# Robot_Psoc.net
KiCad netlist of a schematic drawn in EAGLE
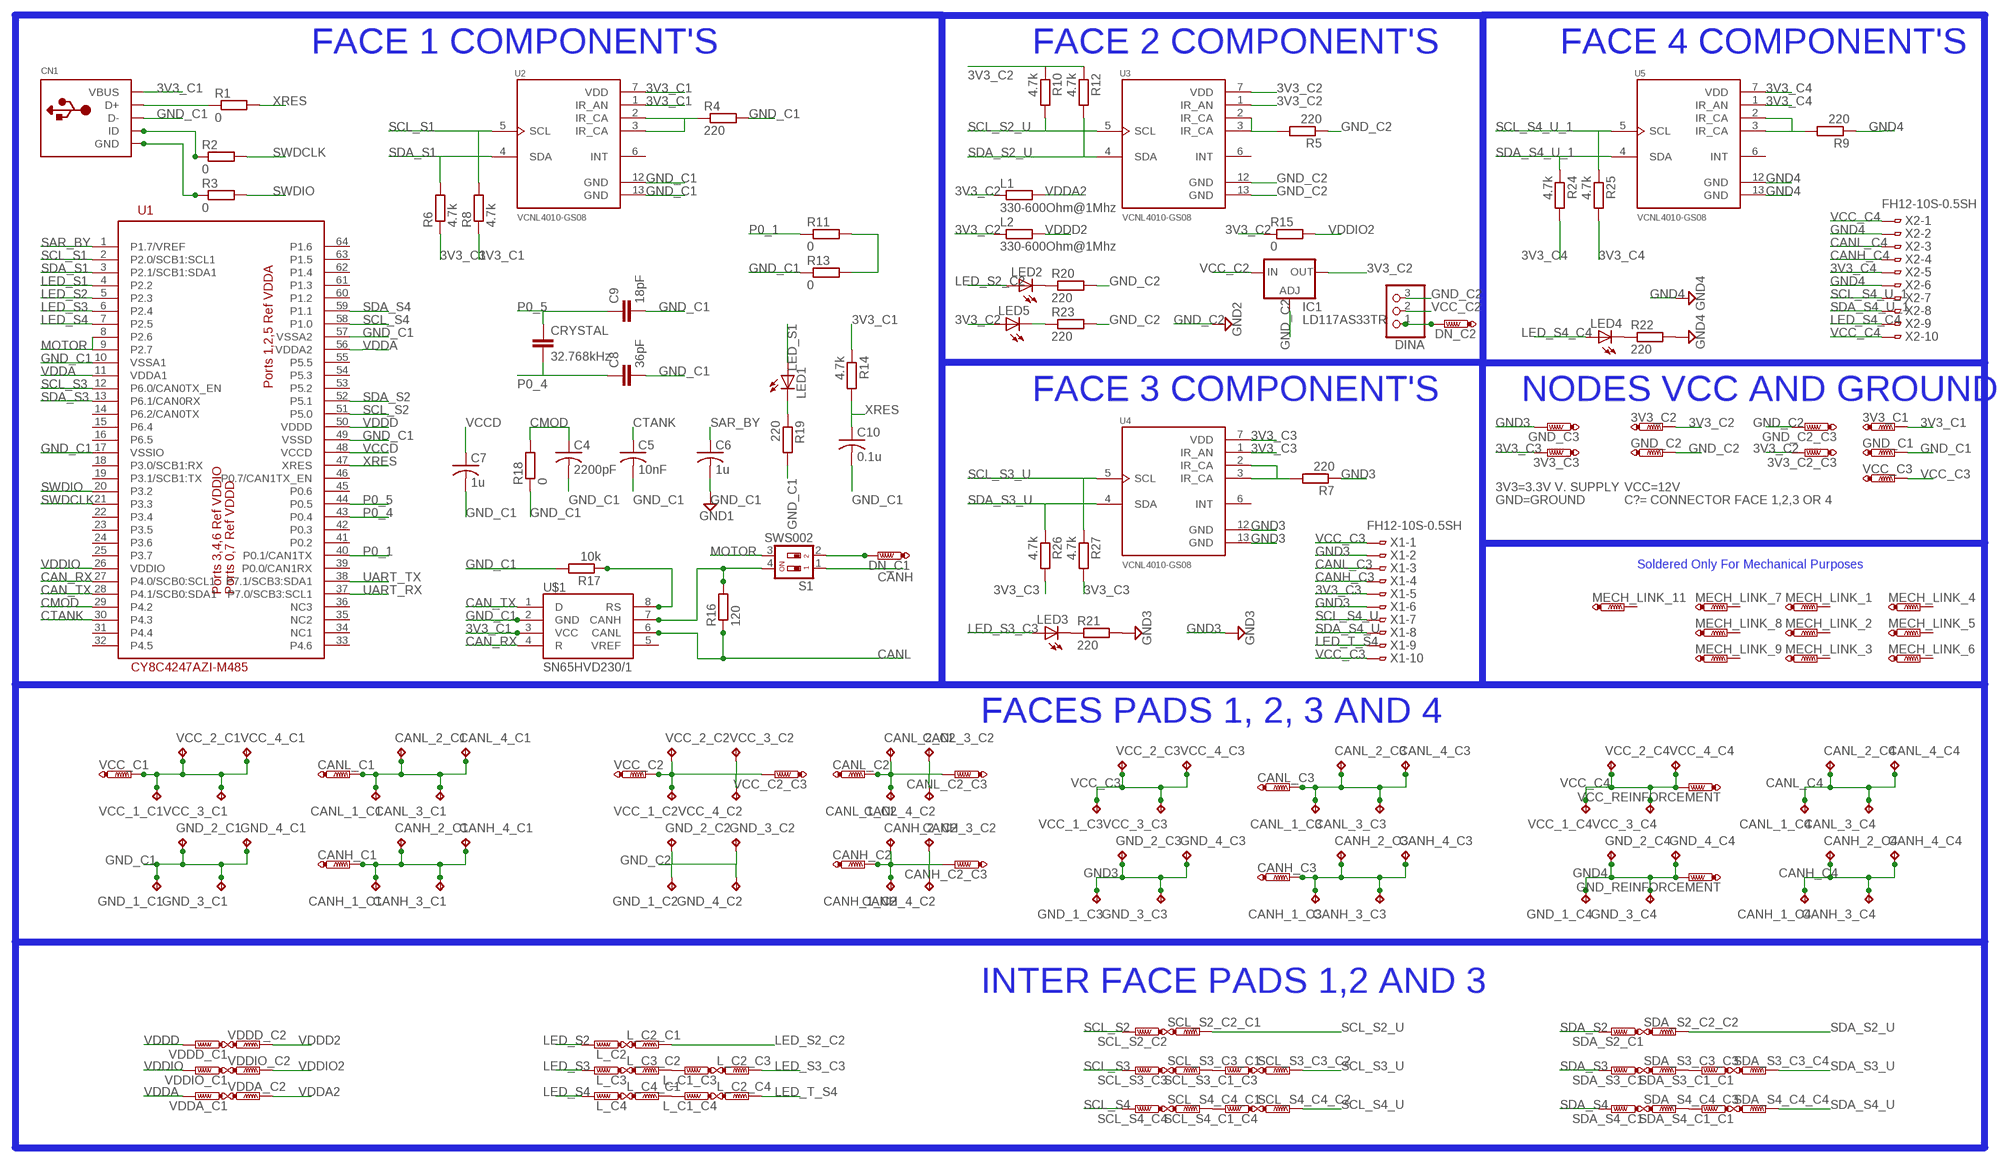
[diagram p0: schematic, sheet 1]

(export (version "E")
  (design (tool "Eeschema 10.0.6"))
  (components
    (comp (ref "3V3_C1")
      (value "PTR1TP11R")
      (footprint "eagle-import:TP11R")
      (libsource (lib "eagle-import") (part "PTR1TP11R"))
    )
    (comp (ref "3V3_C2")
      (value "PTR1TP11R")
      (footprint "eagle-import:TP11R")
      (libsource (lib "eagle-import") (part "PTR1TP11R"))
    )
    (comp (ref "3V3_C2_C3")
      (value "PTR1TP11R")
      (footprint "eagle-import:TP11R")
      (libsource (lib "eagle-import") (part "PTR1TP11R"))
    )
    (comp (ref "3V3_C3")
      (value "PTR1TP11R")
      (footprint "eagle-import:TP11R")
      (libsource (lib "eagle-import") (part "PTR1TP11R"))
    )
    (comp (ref "C4")
      (value "2200pF")
      (footprint "eagle-import:C0805")
      (libsource (lib "eagle-import") (part "C-USC0805"))
    )
    (comp (ref "C5")
      (value "10nF")
      (footprint "eagle-import:C0805")
      (libsource (lib "eagle-import") (part "C-USC0805"))
    )
    (comp (ref "C6")
      (value "1u")
      (footprint "eagle-import:C0805")
      (libsource (lib "eagle-import") (part "C-USC0805"))
    )
    (comp (ref "C7")
      (value "1u")
      (footprint "eagle-import:C0805")
      (libsource (lib "eagle-import") (part "C-USC0805"))
    )
    (comp (ref "C8")
      (value "36pF")
      (footprint "eagle-import:C0805")
      (libsource (lib "eagle-import") (part "C-EUC0805"))
    )
    (comp (ref "C9")
      (value "18pF")
      (footprint "eagle-import:C0805")
      (libsource (lib "eagle-import") (part "C-EUC0805"))
    )
    (comp (ref "C10")
      (value "0.1u")
      (footprint "eagle-import:C0805")
      (libsource (lib "eagle-import") (part "C-USC0805"))
    )
    (comp (ref "CANH_1_C1")
      (value "TPB2,54")
      (footprint "eagle-import:B2,54")
      (libsource (lib "eagle-import") (part "TPB2,54"))
    )
    (comp (ref "CANH_1_C2")
      (value "TPB2,54")
      (footprint "eagle-import:B2,54")
      (libsource (lib "eagle-import") (part "TPB2,54"))
    )
    (comp (ref "CANH_1_C3")
      (value "TPB2,54")
      (footprint "eagle-import:B2,54")
      (libsource (lib "eagle-import") (part "TPB2,54"))
    )
    (comp (ref "CANH_1_C4")
      (value "TPB2,54")
      (footprint "eagle-import:B2,54")
      (libsource (lib "eagle-import") (part "TPB2,54"))
    )
    (comp (ref "CANH_2_C1")
      (value "TPB2,54")
      (footprint "eagle-import:B2,54")
      (libsource (lib "eagle-import") (part "TPB2,54"))
    )
    (comp (ref "CANH_2_C2")
      (value "TPB2,54")
      (footprint "eagle-import:B2,54")
      (libsource (lib "eagle-import") (part "TPB2,54"))
    )
    (comp (ref "CANH_2_C3")
      (value "TPB2,54")
      (footprint "eagle-import:B2,54")
      (libsource (lib "eagle-import") (part "TPB2,54"))
    )
    (comp (ref "CANH_2_C4")
      (value "TPB2,54")
      (footprint "eagle-import:B2,54")
      (libsource (lib "eagle-import") (part "TPB2,54"))
    )
    (comp (ref "CANH_3_C1")
      (value "TPB2,54")
      (footprint "eagle-import:B2,54")
      (libsource (lib "eagle-import") (part "TPB2,54"))
    )
    (comp (ref "CANH_3_C2")
      (value "TPB2,54")
      (footprint "eagle-import:B2,54")
      (libsource (lib "eagle-import") (part "TPB2,54"))
    )
    (comp (ref "CANH_3_C3")
      (value "TPB2,54")
      (footprint "eagle-import:B2,54")
      (libsource (lib "eagle-import") (part "TPB2,54"))
    )
    (comp (ref "CANH_3_C4")
      (value "TPB2,54")
      (footprint "eagle-import:B2,54")
      (libsource (lib "eagle-import") (part "TPB2,54"))
    )
    (comp (ref "CANH_4_C1")
      (value "TPB2,54")
      (footprint "eagle-import:B2,54")
      (libsource (lib "eagle-import") (part "TPB2,54"))
    )
    (comp (ref "CANH_4_C2")
      (value "TPB2,54")
      (footprint "eagle-import:B2,54")
      (libsource (lib "eagle-import") (part "TPB2,54"))
    )
    (comp (ref "CANH_4_C3")
      (value "TPB2,54")
      (footprint "eagle-import:B2,54")
      (libsource (lib "eagle-import") (part "TPB2,54"))
    )
    (comp (ref "CANH_4_C4")
      (value "TPB2,54")
      (footprint "eagle-import:B2,54")
      (libsource (lib "eagle-import") (part "TPB2,54"))
    )
    (comp (ref "CANH_C1")
      (value "PTR1TP11R")
      (footprint "eagle-import:TP11R")
      (libsource (lib "eagle-import") (part "PTR1TP11R"))
    )
    (comp (ref "CANH_C2")
      (value "PTR1TP11R")
      (footprint "eagle-import:TP11R")
      (libsource (lib "eagle-import") (part "PTR1TP11R"))
    )
    (comp (ref "CANH_C2_C3")
      (value "PTR1TP11R")
      (footprint "eagle-import:TP11R")
      (libsource (lib "eagle-import") (part "PTR1TP11R"))
    )
    (comp (ref "CANH_C3")
      (value "PTR1TP11R")
      (footprint "eagle-import:TP11R")
      (libsource (lib "eagle-import") (part "PTR1TP11R"))
    )
    (comp (ref "CANL_1_C1")
      (value "TPB2,54")
      (footprint "eagle-import:B2,54")
      (libsource (lib "eagle-import") (part "TPB2,54"))
    )
    (comp (ref "CANL_1_C2")
      (value "TPB2,54")
      (footprint "eagle-import:B2,54")
      (libsource (lib "eagle-import") (part "TPB2,54"))
    )
    (comp (ref "CANL_1_C3")
      (value "TPB2,54")
      (footprint "eagle-import:B2,54")
      (libsource (lib "eagle-import") (part "TPB2,54"))
    )
    (comp (ref "CANL_1_C4")
      (value "TPB2,54")
      (footprint "eagle-import:B2,54")
      (libsource (lib "eagle-import") (part "TPB2,54"))
    )
    (comp (ref "CANL_2_C1")
      (value "TPB2,54")
      (footprint "eagle-import:B2,54")
      (libsource (lib "eagle-import") (part "TPB2,54"))
    )
    (comp (ref "CANL_2_C2")
      (value "TPB2,54")
      (footprint "eagle-import:B2,54")
      (libsource (lib "eagle-import") (part "TPB2,54"))
    )
    (comp (ref "CANL_2_C3")
      (value "TPB2,54")
      (footprint "eagle-import:B2,54")
      (libsource (lib "eagle-import") (part "TPB2,54"))
    )
    (comp (ref "CANL_2_C4")
      (value "TPB2,54")
      (footprint "eagle-import:B2,54")
      (libsource (lib "eagle-import") (part "TPB2,54"))
    )
    (comp (ref "CANL_3_C1")
      (value "TPB2,54")
      (footprint "eagle-import:B2,54")
      (libsource (lib "eagle-import") (part "TPB2,54"))
    )
    (comp (ref "CANL_3_C2")
      (value "TPB2,54")
      (footprint "eagle-import:B2,54")
      (libsource (lib "eagle-import") (part "TPB2,54"))
    )
    (comp (ref "CANL_3_C3")
      (value "TPB2,54")
      (footprint "eagle-import:B2,54")
      (libsource (lib "eagle-import") (part "TPB2,54"))
    )
    (comp (ref "CANL_3_C4")
      (value "TPB2,54")
      (footprint "eagle-import:B2,54")
      (libsource (lib "eagle-import") (part "TPB2,54"))
    )
    (comp (ref "CANL_4_C1")
      (value "TPB2,54")
      (footprint "eagle-import:B2,54")
      (libsource (lib "eagle-import") (part "TPB2,54"))
    )
    (comp (ref "CANL_4_C2")
      (value "TPB2,54")
      (footprint "eagle-import:B2,54")
      (libsource (lib "eagle-import") (part "TPB2,54"))
    )
    (comp (ref "CANL_4_C3")
      (value "TPB2,54")
      (footprint "eagle-import:B2,54")
      (libsource (lib "eagle-import") (part "TPB2,54"))
    )
    (comp (ref "CANL_4_C4")
      (value "TPB2,54")
      (footprint "eagle-import:B2,54")
      (libsource (lib "eagle-import") (part "TPB2,54"))
    )
    (comp (ref "CANL_C1")
      (value "PTR1TP11R")
      (footprint "eagle-import:TP11R")
      (libsource (lib "eagle-import") (part "PTR1TP11R"))
    )
    (comp (ref "CANL_C2")
      (value "PTR1TP11R")
      (footprint "eagle-import:TP11R")
      (libsource (lib "eagle-import") (part "PTR1TP11R"))
    )
    (comp (ref "CANL_C2_C3")
      (value "PTR1TP11R")
      (footprint "eagle-import:TP11R")
      (libsource (lib "eagle-import") (part "PTR1TP11R"))
    )
    (comp (ref "CANL_C3")
      (value "PTR1TP11R")
      (footprint "eagle-import:TP11R")
      (libsource (lib "eagle-import") (part "PTR1TP11R"))
    )
    (comp (ref "CN1")
      (value "USBMINIB")
      (footprint "eagle-import:USB-MINIB")
      (libsource (lib "eagle-import") (part "USBMINIB"))
    )
    (comp (ref "CRYSTAL")
      (value "32.768kHz")
      (footprint "eagle-import:C0603")
      (libsource (lib "eagle-import") (part "C-EUC0603"))
    )
    (comp (ref "DINA")
      (value "PINHD-1X3")
      (footprint "eagle-import:1X03")
      (libsource (lib "eagle-import") (part "PINHD-1X3"))
    )
    (comp (ref "DN_C1")
      (value "PTR1TP11R")
      (footprint "eagle-import:TP11R")
      (libsource (lib "eagle-import") (part "PTR1TP11R"))
    )
    (comp (ref "DN_C2")
      (value "PTR1TP11R")
      (footprint "eagle-import:TP11R")
      (libsource (lib "eagle-import") (part "PTR1TP11R"))
    )
    (comp (ref "GND_1_C1")
      (value "TPB2,54")
      (footprint "eagle-import:B2,54")
      (libsource (lib "eagle-import") (part "TPB2,54"))
    )
    (comp (ref "GND_1_C2")
      (value "TPB2,54")
      (footprint "eagle-import:B2,54")
      (libsource (lib "eagle-import") (part "TPB2,54"))
    )
    (comp (ref "GND_1_C3")
      (value "TPB2,54")
      (footprint "eagle-import:B2,54")
      (libsource (lib "eagle-import") (part "TPB2,54"))
    )
    (comp (ref "GND_1_C4")
      (value "TPB2,54")
      (footprint "eagle-import:B2,54")
      (libsource (lib "eagle-import") (part "TPB2,54"))
    )
    (comp (ref "GND_2_C1")
      (value "TPB2,54")
      (footprint "eagle-import:B2,54")
      (libsource (lib "eagle-import") (part "TPB2,54"))
    )
    (comp (ref "GND_2_C2")
      (value "TPB2,54")
      (footprint "eagle-import:B2,54")
      (libsource (lib "eagle-import") (part "TPB2,54"))
    )
    (comp (ref "GND_2_C3")
      (value "TPB2,54")
      (footprint "eagle-import:B2,54")
      (libsource (lib "eagle-import") (part "TPB2,54"))
    )
    (comp (ref "GND_2_C4")
      (value "TPB2,54")
      (footprint "eagle-import:B2,54")
      (libsource (lib "eagle-import") (part "TPB2,54"))
    )
    (comp (ref "GND_3_C1")
      (value "TPB2,54")
      (footprint "eagle-import:B2,54")
      (libsource (lib "eagle-import") (part "TPB2,54"))
    )
    (comp (ref "GND_3_C2")
      (value "TPB2,54")
      (footprint "eagle-import:B2,54")
      (libsource (lib "eagle-import") (part "TPB2,54"))
    )
    (comp (ref "GND_3_C3")
      (value "TPB2,54")
      (footprint "eagle-import:B2,54")
      (libsource (lib "eagle-import") (part "TPB2,54"))
    )
    (comp (ref "GND_3_C4")
      (value "TPB2,54")
      (footprint "eagle-import:B2,54")
      (libsource (lib "eagle-import") (part "TPB2,54"))
    )
    (comp (ref "GND_4_C1")
      (value "TPB2,54")
      (footprint "eagle-import:B2,54")
      (libsource (lib "eagle-import") (part "TPB2,54"))
    )
    (comp (ref "GND_4_C2")
      (value "TPB2,54")
      (footprint "eagle-import:B2,54")
      (libsource (lib "eagle-import") (part "TPB2,54"))
    )
    (comp (ref "GND_4_C3")
      (value "TPB2,54")
      (footprint "eagle-import:B2,54")
      (libsource (lib "eagle-import") (part "TPB2,54"))
    )
    (comp (ref "GND_4_C4")
      (value "TPB2,54")
      (footprint "eagle-import:B2,54")
      (libsource (lib "eagle-import") (part "TPB2,54"))
    )
    (comp (ref "GND_C1")
      (value "PTR1TP11R")
      (footprint "eagle-import:TP11R")
      (libsource (lib "eagle-import") (part "PTR1TP11R"))
    )
    (comp (ref "GND_C2")
      (value "PTR1TP11R")
      (footprint "eagle-import:TP11R")
      (libsource (lib "eagle-import") (part "PTR1TP11R"))
    )
    (comp (ref "GND_C2_C3")
      (value "PTR1TP11R")
      (footprint "eagle-import:TP11R")
      (libsource (lib "eagle-import") (part "PTR1TP11R"))
    )
    (comp (ref "GND_C3")
      (value "PTR1TP11R")
      (footprint "eagle-import:TP11R")
      (libsource (lib "eagle-import") (part "PTR1TP11R"))
    )
    (comp (ref "GND_REINFORCEMENT")
      (value "PTR1TP11R")
      (footprint "eagle-import:TP11R")
      (libsource (lib "eagle-import") (part "PTR1TP11R"))
    )
    (comp (ref "IC1")
      (value "LD117AS33TR")
      (footprint "eagle-import:SOT223")
      (libsource (lib "eagle-import") (part "LD117A?S33TR"))
    )
    (comp (ref "L1")
      (value "330-600Ohm@1Mhz")
      (footprint "eagle-import:R0805")
      (libsource (lib "eagle-import") (part "R-EU_R0805"))
    )
    (comp (ref "L2")
      (value "330-600Ohm@1Mhz")
      (footprint "eagle-import:R0805")
      (libsource (lib "eagle-import") (part "R-EU_R0805"))
    )
    (comp (ref "LED1")
      (value "LEDCHIPLED_0805")
      (footprint "eagle-import:CHIPLED_0805")
      (libsource (lib "eagle-import") (part "LEDCHIPLED_0805"))
    )
    (comp (ref "LED2")
      (value "LEDCHIPLED_0805")
      (footprint "eagle-import:CHIPLED_0805")
      (libsource (lib "eagle-import") (part "LEDCHIPLED_0805"))
    )
    (comp (ref "LED3")
      (value "LEDCHIPLED_0805")
      (footprint "eagle-import:CHIPLED_0805")
      (libsource (lib "eagle-import") (part "LEDCHIPLED_0805"))
    )
    (comp (ref "LED4")
      (value "LEDCHIPLED_0805")
      (footprint "eagle-import:CHIPLED_0805")
      (libsource (lib "eagle-import") (part "LEDCHIPLED_0805"))
    )
    (comp (ref "LED5")
      (value "LEDCHIPLED_0805")
      (footprint "eagle-import:CHIPLED_0805")
      (libsource (lib "eagle-import") (part "LEDCHIPLED_0805"))
    )
    (comp (ref "L_C1_C3")
      (value "PTR1TP11R")
      (footprint "eagle-import:TP11R")
      (libsource (lib "eagle-import") (part "PTR1TP11R"))
    )
    (comp (ref "L_C1_C4")
      (value "PTR1TP11R")
      (footprint "eagle-import:TP11R")
      (libsource (lib "eagle-import") (part "PTR1TP11R"))
    )
    (comp (ref "L_C2")
      (value "PTR1TP11R")
      (footprint "eagle-import:TP11R")
      (libsource (lib "eagle-import") (part "PTR1TP11R"))
    )
    (comp (ref "L_C2_C1")
      (value "PTR1TP11R")
      (footprint "eagle-import:TP11R")
      (libsource (lib "eagle-import") (part "PTR1TP11R"))
    )
    (comp (ref "L_C2_C3")
      (value "PTR1TP11R")
      (footprint "eagle-import:TP11R")
      (libsource (lib "eagle-import") (part "PTR1TP11R"))
    )
    (comp (ref "L_C2_C4")
      (value "PTR1TP11R")
      (footprint "eagle-import:TP11R")
      (libsource (lib "eagle-import") (part "PTR1TP11R"))
    )
    (comp (ref "L_C3")
      (value "PTR1TP11R")
      (footprint "eagle-import:TP11R")
      (libsource (lib "eagle-import") (part "PTR1TP11R"))
    )
    (comp (ref "L_C3_C2")
      (value "PTR1TP11R")
      (footprint "eagle-import:TP11R")
      (libsource (lib "eagle-import") (part "PTR1TP11R"))
    )
    (comp (ref "L_C4")
      (value "PTR1TP11R")
      (footprint "eagle-import:TP11R")
      (libsource (lib "eagle-import") (part "PTR1TP11R"))
    )
    (comp (ref "L_C4_C1")
      (value "PTR1TP11R")
      (footprint "eagle-import:TP11R")
      (libsource (lib "eagle-import") (part "PTR1TP11R"))
    )
    (comp (ref "MECH_LINK_1")
      (value "PTR1TP11R")
      (footprint "eagle-import:TP11R")
      (libsource (lib "eagle-import") (part "PTR1TP11R"))
    )
    (comp (ref "MECH_LINK_2")
      (value "PTR1TP11R")
      (footprint "eagle-import:TP11R")
      (libsource (lib "eagle-import") (part "PTR1TP11R"))
    )
    (comp (ref "MECH_LINK_3")
      (value "PTR1TP11R")
      (footprint "eagle-import:TP11R")
      (libsource (lib "eagle-import") (part "PTR1TP11R"))
    )
    (comp (ref "MECH_LINK_4")
      (value "PTR1TP11R")
      (footprint "eagle-import:TP11R")
      (libsource (lib "eagle-import") (part "PTR1TP11R"))
    )
    (comp (ref "MECH_LINK_5")
      (value "PTR1TP11R")
      (footprint "eagle-import:TP11R")
      (libsource (lib "eagle-import") (part "PTR1TP11R"))
    )
    (comp (ref "MECH_LINK_6")
      (value "PTR1TP11R")
      (footprint "eagle-import:TP11R")
      (libsource (lib "eagle-import") (part "PTR1TP11R"))
    )
    (comp (ref "MECH_LINK_7")
      (value "PTR1TP11R")
      (footprint "eagle-import:TP11R")
      (libsource (lib "eagle-import") (part "PTR1TP11R"))
    )
    (comp (ref "MECH_LINK_8")
      (value "PTR1TP11R")
      (footprint "eagle-import:TP11R")
      (libsource (lib "eagle-import") (part "PTR1TP11R"))
    )
    (comp (ref "MECH_LINK_9")
      (value "PTR1TP11R")
      (footprint "eagle-import:TP11R")
      (libsource (lib "eagle-import") (part "PTR1TP11R"))
    )
    (comp (ref "MECH_LINK_11")
      (value "PTR1TP11R")
      (footprint "eagle-import:TP11R")
      (libsource (lib "eagle-import") (part "PTR1TP11R"))
    )
    (comp (ref "R1")
      (value "0")
      (footprint "eagle-import:R0805")
      (libsource (lib "eagle-import") (part "R-EU_R0805"))
    )
    (comp (ref "R2")
      (value "0")
      (footprint "eagle-import:R0805")
      (libsource (lib "eagle-import") (part "R-EU_R0805"))
    )
    (comp (ref "R3")
      (value "0")
      (footprint "eagle-import:R0805")
      (libsource (lib "eagle-import") (part "R-EU_R0805"))
    )
    (comp (ref "R4")
      (value "220")
      (footprint "eagle-import:R0805")
      (libsource (lib "eagle-import") (part "R-EU_R0805"))
    )
    (comp (ref "R5")
      (value "220")
      (footprint "eagle-import:R0805")
      (libsource (lib "eagle-import") (part "R-EU_R0805"))
    )
    (comp (ref "R6")
      (value "4.7k")
      (footprint "eagle-import:R0805")
      (libsource (lib "eagle-import") (part "R-EU_R0805"))
    )
    (comp (ref "R7")
      (value "220")
      (footprint "eagle-import:R0805")
      (libsource (lib "eagle-import") (part "R-EU_R0805"))
    )
    (comp (ref "R8")
      (value "4.7k")
      (footprint "eagle-import:R0805")
      (libsource (lib "eagle-import") (part "R-EU_R0805"))
    )
    (comp (ref "R9")
      (value "220")
      (footprint "eagle-import:R0805")
      (libsource (lib "eagle-import") (part "R-EU_R0805"))
    )
    (comp (ref "R10")
      (value "4.7k")
      (footprint "eagle-import:R0805")
      (libsource (lib "eagle-import") (part "R-EU_R0805"))
    )
    (comp (ref "R11")
      (value "0")
      (footprint "eagle-import:R0805")
      (libsource (lib "eagle-import") (part "R-EU_R0805"))
    )
    (comp (ref "R12")
      (value "4.7k")
      (footprint "eagle-import:R0805")
      (libsource (lib "eagle-import") (part "R-EU_R0805"))
    )
    (comp (ref "R13")
      (value "0")
      (footprint "eagle-import:R0805")
      (libsource (lib "eagle-import") (part "R-EU_R0805"))
    )
    (comp (ref "R14")
      (value "4.7k")
      (footprint "eagle-import:R0805")
      (libsource (lib "eagle-import") (part "R-EU_R0805"))
    )
    (comp (ref "R15")
      (value "0")
      (footprint "eagle-import:R0805")
      (libsource (lib "eagle-import") (part "R-EU_R0805"))
    )
    (comp (ref "R16")
      (value "120")
      (footprint "eagle-import:R0805")
      (libsource (lib "eagle-import") (part "R-EU_R0805"))
    )
    (comp (ref "R17")
      (value "10k")
      (footprint "eagle-import:R0805")
      (libsource (lib "eagle-import") (part "R-EU_R0805"))
    )
    (comp (ref "R18")
      (value "0")
      (footprint "eagle-import:R0805")
      (libsource (lib "eagle-import") (part "R-EU_R0805"))
    )
    (comp (ref "R19")
      (value "220")
      (footprint "eagle-import:R0805")
      (libsource (lib "eagle-import") (part "R-EU_R0805"))
    )
    (comp (ref "R20")
      (value "220")
      (footprint "eagle-import:R0805")
      (libsource (lib "eagle-import") (part "R-EU_R0805"))
    )
    (comp (ref "R21")
      (value "220")
      (footprint "eagle-import:R0805")
      (libsource (lib "eagle-import") (part "R-EU_R0805"))
    )
    (comp (ref "R22")
      (value "220")
      (footprint "eagle-import:R0805")
      (libsource (lib "eagle-import") (part "R-EU_R0805"))
    )
    (comp (ref "R23")
      (value "220")
      (footprint "eagle-import:R0805")
      (libsource (lib "eagle-import") (part "R-EU_R0805"))
    )
    (comp (ref "R24")
      (value "4.7k")
      (footprint "eagle-import:R0805")
      (libsource (lib "eagle-import") (part "R-EU_R0805"))
    )
    (comp (ref "R25")
      (value "4.7k")
      (footprint "eagle-import:R0805")
      (libsource (lib "eagle-import") (part "R-EU_R0805"))
    )
    (comp (ref "R26")
      (value "4.7k")
      (footprint "eagle-import:R0805")
      (libsource (lib "eagle-import") (part "R-EU_R0805"))
    )
    (comp (ref "R27")
      (value "4.7k")
      (footprint "eagle-import:R0805")
      (libsource (lib "eagle-import") (part "R-EU_R0805"))
    )
    (comp (ref "S1")
      (value "SWS002")
      (footprint "eagle-import:SMS-002")
      (libsource (lib "eagle-import") (part "SWS002"))
    )
    (comp (ref "SCL_S2_C2")
      (value "PTR1TP11R")
      (footprint "eagle-import:TP11R")
      (libsource (lib "eagle-import") (part "PTR1TP11R"))
    )
    (comp (ref "SCL_S2_C2_C1")
      (value "PTR1TP11R")
      (footprint "eagle-import:TP11R")
      (libsource (lib "eagle-import") (part "PTR1TP11R"))
    )
    (comp (ref "SCL_S3_C1_C3")
      (value "PTR1TP11R")
      (footprint "eagle-import:TP11R")
      (libsource (lib "eagle-import") (part "PTR1TP11R"))
    )
    (comp (ref "SCL_S3_C3")
      (value "PTR1TP11R")
      (footprint "eagle-import:TP11R")
      (libsource (lib "eagle-import") (part "PTR1TP11R"))
    )
    (comp (ref "SCL_S3_C3_C1")
      (value "PTR1TP11R")
      (footprint "eagle-import:TP11R")
      (libsource (lib "eagle-import") (part "PTR1TP11R"))
    )
    (comp (ref "SCL_S3_C3_C2")
      (value "PTR1TP11R")
      (footprint "eagle-import:TP11R")
      (libsource (lib "eagle-import") (part "PTR1TP11R"))
    )
    (comp (ref "SCL_S4_C1_C4")
      (value "PTR1TP11R")
      (footprint "eagle-import:TP11R")
      (libsource (lib "eagle-import") (part "PTR1TP11R"))
    )
    (comp (ref "SCL_S4_C4")
      (value "PTR1TP11R")
      (footprint "eagle-import:TP11R")
      (libsource (lib "eagle-import") (part "PTR1TP11R"))
    )
    (comp (ref "SCL_S4_C4_C1")
      (value "PTR1TP11R")
      (footprint "eagle-import:TP11R")
      (libsource (lib "eagle-import") (part "PTR1TP11R"))
    )
    (comp (ref "SCL_S4_C4_C2")
      (value "PTR1TP11R")
      (footprint "eagle-import:TP11R")
      (libsource (lib "eagle-import") (part "PTR1TP11R"))
    )
    (comp (ref "SDA_S2_C1")
      (value "PTR1TP11R")
      (footprint "eagle-import:TP11R")
      (libsource (lib "eagle-import") (part "PTR1TP11R"))
    )
    (comp (ref "SDA_S2_C2_C2")
      (value "PTR1TP11R")
      (footprint "eagle-import:TP11R")
      (libsource (lib "eagle-import") (part "PTR1TP11R"))
    )
    (comp (ref "SDA_S3_C1")
      (value "PTR1TP11R")
      (footprint "eagle-import:TP11R")
      (libsource (lib "eagle-import") (part "PTR1TP11R"))
    )
    (comp (ref "SDA_S3_C1_C1")
      (value "PTR1TP11R")
      (footprint "eagle-import:TP11R")
      (libsource (lib "eagle-import") (part "PTR1TP11R"))
    )
    (comp (ref "SDA_S3_C3_C3")
      (value "PTR1TP11R")
      (footprint "eagle-import:TP11R")
      (libsource (lib "eagle-import") (part "PTR1TP11R"))
    )
    (comp (ref "SDA_S3_C3_C4")
      (value "PTR1TP11R")
      (footprint "eagle-import:TP11R")
      (libsource (lib "eagle-import") (part "PTR1TP11R"))
    )
    (comp (ref "SDA_S4_C1")
      (value "PTR1TP11R")
      (footprint "eagle-import:TP11R")
      (libsource (lib "eagle-import") (part "PTR1TP11R"))
    )
    (comp (ref "SDA_S4_C1_C1")
      (value "PTR1TP11R")
      (footprint "eagle-import:TP11R")
      (libsource (lib "eagle-import") (part "PTR1TP11R"))
    )
    (comp (ref "SDA_S4_C4_C3")
      (value "PTR1TP11R")
      (footprint "eagle-import:TP11R")
      (libsource (lib "eagle-import") (part "PTR1TP11R"))
    )
    (comp (ref "SDA_S4_C4_C4")
      (value "PTR1TP11R")
      (footprint "eagle-import:TP11R")
      (libsource (lib "eagle-import") (part "PTR1TP11R"))
    )
    (comp (ref "U$1")
      (value "SN65HVD230/1")
      (footprint "eagle-import:SO8")
      (libsource (lib "eagle-import") (part "SN65HVD230/1"))
    )
    (comp (ref "U1")
      (value "CY8C4247AZI-M485")
      (footprint "eagle-import:TQFP64-10X10")
      (libsource (lib "eagle-import") (part "CY8C4247AZI-M485"))
    )
    (comp (ref "U2")
      (value "VCNL4010-GS08")
      (footprint "eagle-import:XDCR_VCNL4010-GS08")
      (libsource (lib "eagle-import") (part "VCNL4010-GS08"))
    )
    (comp (ref "U3")
      (value "VCNL4010-GS08")
      (footprint "eagle-import:XDCR_VCNL4010-GS08")
      (libsource (lib "eagle-import") (part "VCNL4010-GS08"))
    )
    (comp (ref "U4")
      (value "VCNL4010-GS08")
      (footprint "eagle-import:XDCR_VCNL4010-GS08")
      (libsource (lib "eagle-import") (part "VCNL4010-GS08"))
    )
    (comp (ref "U5")
      (value "VCNL4010-GS08")
      (footprint "eagle-import:XDCR_VCNL4010-GS08")
      (libsource (lib "eagle-import") (part "VCNL4010-GS08"))
    )
    (comp (ref "VCC_1_C1")
      (value "TPB2,54")
      (footprint "eagle-import:B2,54")
      (libsource (lib "eagle-import") (part "TPB2,54"))
    )
    (comp (ref "VCC_1_C2")
      (value "TPB2,54")
      (footprint "eagle-import:B2,54")
      (libsource (lib "eagle-import") (part "TPB2,54"))
    )
    (comp (ref "VCC_1_C3")
      (value "TPB2,54")
      (footprint "eagle-import:B2,54")
      (libsource (lib "eagle-import") (part "TPB2,54"))
    )
    (comp (ref "VCC_1_C4")
      (value "TPB2,54")
      (footprint "eagle-import:B2,54")
      (libsource (lib "eagle-import") (part "TPB2,54"))
    )
    (comp (ref "VCC_2_C1")
      (value "TPB2,54")
      (footprint "eagle-import:B2,54")
      (libsource (lib "eagle-import") (part "TPB2,54"))
    )
    (comp (ref "VCC_2_C2")
      (value "TPB2,54")
      (footprint "eagle-import:B2,54")
      (libsource (lib "eagle-import") (part "TPB2,54"))
    )
    (comp (ref "VCC_2_C3")
      (value "TPB2,54")
      (footprint "eagle-import:B2,54")
      (libsource (lib "eagle-import") (part "TPB2,54"))
    )
    (comp (ref "VCC_2_C4")
      (value "TPB2,54")
      (footprint "eagle-import:B2,54")
      (libsource (lib "eagle-import") (part "TPB2,54"))
    )
    (comp (ref "VCC_3_C1")
      (value "TPB2,54")
      (footprint "eagle-import:B2,54")
      (libsource (lib "eagle-import") (part "TPB2,54"))
    )
    (comp (ref "VCC_3_C2")
      (value "TPB2,54")
      (footprint "eagle-import:B2,54")
      (libsource (lib "eagle-import") (part "TPB2,54"))
    )
    (comp (ref "VCC_3_C3")
      (value "TPB2,54")
      (footprint "eagle-import:B2,54")
      (libsource (lib "eagle-import") (part "TPB2,54"))
    )
    (comp (ref "VCC_3_C4")
      (value "TPB2,54")
      (footprint "eagle-import:B2,54")
      (libsource (lib "eagle-import") (part "TPB2,54"))
    )
    (comp (ref "VCC_4_C1")
      (value "TPB2,54")
      (footprint "eagle-import:B2,54")
      (libsource (lib "eagle-import") (part "TPB2,54"))
    )
    (comp (ref "VCC_4_C2")
      (value "TPB2,54")
      (footprint "eagle-import:B2,54")
      (libsource (lib "eagle-import") (part "TPB2,54"))
    )
    (comp (ref "VCC_4_C3")
      (value "TPB2,54")
      (footprint "eagle-import:B2,54")
      (libsource (lib "eagle-import") (part "TPB2,54"))
    )
    (comp (ref "VCC_4_C4")
      (value "TPB2,54")
      (footprint "eagle-import:B2,54")
      (libsource (lib "eagle-import") (part "TPB2,54"))
    )
    (comp (ref "VCC_C1")
      (value "PTR1TP11R")
      (footprint "eagle-import:TP11R")
      (libsource (lib "eagle-import") (part "PTR1TP11R"))
    )
    (comp (ref "VCC_C2")
      (value "PTR1TP11R")
      (footprint "eagle-import:TP11R")
      (libsource (lib "eagle-import") (part "PTR1TP11R"))
    )
    (comp (ref "VCC_C2_C3")
      (value "PTR1TP11R")
      (footprint "eagle-import:TP11R")
      (libsource (lib "eagle-import") (part "PTR1TP11R"))
    )
    (comp (ref "VCC_C3")
      (value "PTR1TP11R")
      (footprint "eagle-import:TP11R")
      (libsource (lib "eagle-import") (part "PTR1TP11R"))
    )
    (comp (ref "VCC_REINFORCEMENT")
      (value "PTR1TP11R")
      (footprint "eagle-import:TP11R")
      (libsource (lib "eagle-import") (part "PTR1TP11R"))
    )
    (comp (ref "VDDA_C1")
      (value "PTR1TP11R")
      (footprint "eagle-import:TP11R")
      (libsource (lib "eagle-import") (part "PTR1TP11R"))
    )
    (comp (ref "VDDA_C2")
      (value "PTR1TP11R")
      (footprint "eagle-import:TP11R")
      (libsource (lib "eagle-import") (part "PTR1TP11R"))
    )
    (comp (ref "VDDD_C1")
      (value "PTR1TP11R")
      (footprint "eagle-import:TP11R")
      (libsource (lib "eagle-import") (part "PTR1TP11R"))
    )
    (comp (ref "VDDD_C2")
      (value "PTR1TP11R")
      (footprint "eagle-import:TP11R")
      (libsource (lib "eagle-import") (part "PTR1TP11R"))
    )
    (comp (ref "VDDIO_C1")
      (value "PTR1TP11R")
      (footprint "eagle-import:TP11R")
      (libsource (lib "eagle-import") (part "PTR1TP11R"))
    )
    (comp (ref "VDDIO_C2")
      (value "PTR1TP11R")
      (footprint "eagle-import:TP11R")
      (libsource (lib "eagle-import") (part "PTR1TP11R"))
    )
    (comp (ref "X1")
      (value "FH12-10S-0.5SH")
      (footprint "eagle-import:FH12-10S-0.5SH")
      (fields (field (name "MPN") "FH12-10S-0.5SH(55)"))
      (libsource (lib "eagle-import") (part "FH12-10S-0.5SH"))
    )
    (comp (ref "X2")
      (value "FH12-10S-0.5SH")
      (footprint "eagle-import:FH12-10S-0.5SH")
      (fields (field (name "MPN") "FH12-10S-0.5SH(55)"))
      (libsource (lib "eagle-import") (part "FH12-10S-0.5SH"))
    )
  )
  (nets
    (net (code "1") (name "/3V3_C1") (class "Default")
      (node (ref "3V3_C1") (pin "TP") (pinfunction "TP_TP") (pintype "input"))
      (node (ref "CN1") (pin "VBUS") (pinfunction "VBUS_VBUS") (pintype "power_in"))
      (node (ref "R14") (pin "1") (pinfunction "1_1") (pintype "passive"))
      (node (ref "R6") (pin "1") (pinfunction "1_1") (pintype "passive"))
      (node (ref "R8") (pin "1") (pinfunction "1_1") (pintype "passive"))
      (node (ref "U$1") (pin "3") (pinfunction "VCC_3") (pintype "power_in"))
      (node (ref "U2") (pin "1") (pinfunction "IR_AN_1") (pintype "power_in"))
      (node (ref "U2") (pin "7") (pinfunction "VDD_7") (pintype "power_in"))
    )
    (net (code "2") (name "/3V3_C2") (class "Default")
      (node (ref "3V3_C2") (pin "TP") (pinfunction "TP_TP") (pintype "input"))
      (node (ref "3V3_C2_C3") (pin "TP") (pinfunction "TP_TP") (pintype "input"))
      (node (ref "IC1") (pin "4") (pinfunction "OUT_4") (pintype "passive"))
      (node (ref "L1") (pin "1") (pinfunction "1_1") (pintype "passive"))
      (node (ref "L2") (pin "1") (pinfunction "1_1") (pintype "passive"))
      (node (ref "LED5") (pin "A") (pinfunction "A_A") (pintype "passive"))
      (node (ref "R10") (pin "1") (pinfunction "1_1") (pintype "passive"))
      (node (ref "R12") (pin "1") (pinfunction "1_1") (pintype "passive"))
      (node (ref "R15") (pin "1") (pinfunction "1_1") (pintype "passive"))
      (node (ref "U3") (pin "1") (pinfunction "IR_AN_1") (pintype "power_in"))
      (node (ref "U3") (pin "7") (pinfunction "VDD_7") (pintype "power_in"))
    )
    (net (code "3") (name "/3V3_C3") (class "Default")
      (node (ref "3V3_C3") (pin "TP") (pinfunction "TP_TP") (pintype "input"))
      (node (ref "R26") (pin "2") (pinfunction "2_2") (pintype "passive"))
      (node (ref "R27") (pin "2") (pinfunction "2_2") (pintype "passive"))
      (node (ref "U4") (pin "1") (pinfunction "IR_AN_1") (pintype "power_in"))
      (node (ref "U4") (pin "7") (pinfunction "VDD_7") (pintype "power_in"))
      (node (ref "X1") (pin "5") (pinfunction "1_5") (pintype "passive"))
    )
    (net (code "4") (name "/3V3_C4") (class "Default")
      (node (ref "R24") (pin "2") (pinfunction "2_2") (pintype "passive"))
      (node (ref "R25") (pin "2") (pinfunction "2_2") (pintype "passive"))
      (node (ref "U5") (pin "1") (pinfunction "IR_AN_1") (pintype "power_in"))
      (node (ref "U5") (pin "7") (pinfunction "VDD_7") (pintype "power_in"))
      (node (ref "X2") (pin "5") (pinfunction "1_5") (pintype "passive"))
    )
    (net (code "5") (name "/CANH") (class "Default")
      (node (ref "CANH_1_C1") (pin "TP") (pinfunction "TP_TP") (pintype "input"))
      (node (ref "CANH_2_C1") (pin "TP") (pinfunction "TP_TP") (pintype "input"))
      (node (ref "CANH_3_C1") (pin "TP") (pinfunction "TP_TP") (pintype "input"))
      (node (ref "CANH_4_C1") (pin "TP") (pinfunction "TP_TP") (pintype "input"))
      (node (ref "CANH_C1") (pin "TP") (pinfunction "TP_TP") (pintype "input"))
      (node (ref "S1") (pin "1") (pinfunction "1_1") (pintype "passive"))
    )
    (net (code "6") (name "/CANH_C3") (class "Default")
      (node (ref "CANH_1_C3") (pin "TP") (pinfunction "TP_TP") (pintype "input"))
      (node (ref "CANH_2_C3") (pin "TP") (pinfunction "TP_TP") (pintype "input"))
      (node (ref "CANH_3_C3") (pin "TP") (pinfunction "TP_TP") (pintype "input"))
      (node (ref "CANH_4_C3") (pin "TP") (pinfunction "TP_TP") (pintype "input"))
      (node (ref "CANH_C3") (pin "TP") (pinfunction "TP_TP") (pintype "input"))
      (node (ref "X1") (pin "4") (pinfunction "1_4") (pintype "passive"))
    )
    (net (code "7") (name "/CANH_C4") (class "Default")
      (node (ref "CANH_1_C4") (pin "TP") (pinfunction "TP_TP") (pintype "input"))
      (node (ref "CANH_2_C4") (pin "TP") (pinfunction "TP_TP") (pintype "input"))
      (node (ref "CANH_3_C4") (pin "TP") (pinfunction "TP_TP") (pintype "input"))
      (node (ref "CANH_4_C4") (pin "TP") (pinfunction "TP_TP") (pintype "input"))
      (node (ref "X2") (pin "4") (pinfunction "1_4") (pintype "passive"))
    )
    (net (code "8") (name "/CANL") (class "Default")
      (node (ref "CANL_1_C1") (pin "TP") (pinfunction "TP_TP") (pintype "input"))
      (node (ref "CANL_2_C1") (pin "TP") (pinfunction "TP_TP") (pintype "input"))
      (node (ref "CANL_3_C1") (pin "TP") (pinfunction "TP_TP") (pintype "input"))
      (node (ref "CANL_4_C1") (pin "TP") (pinfunction "TP_TP") (pintype "input"))
      (node (ref "CANL_C1") (pin "TP") (pinfunction "TP_TP") (pintype "input"))
      (node (ref "R16") (pin "1") (pinfunction "1_1") (pintype "passive"))
      (node (ref "U$1") (pin "6") (pinfunction "CANL_6") (pintype "bidirectional"))
    )
    (net (code "9") (name "/CANL_C3") (class "Default")
      (node (ref "CANL_1_C3") (pin "TP") (pinfunction "TP_TP") (pintype "input"))
      (node (ref "CANL_2_C3") (pin "TP") (pinfunction "TP_TP") (pintype "input"))
      (node (ref "CANL_3_C3") (pin "TP") (pinfunction "TP_TP") (pintype "input"))
      (node (ref "CANL_4_C3") (pin "TP") (pinfunction "TP_TP") (pintype "input"))
      (node (ref "CANL_C3") (pin "TP") (pinfunction "TP_TP") (pintype "input"))
      (node (ref "X1") (pin "3") (pinfunction "1_3") (pintype "passive"))
    )
    (net (code "10") (name "/CANL_C4") (class "Default")
      (node (ref "CANL_1_C4") (pin "TP") (pinfunction "TP_TP") (pintype "input"))
      (node (ref "CANL_2_C4") (pin "TP") (pinfunction "TP_TP") (pintype "input"))
      (node (ref "CANL_3_C4") (pin "TP") (pinfunction "TP_TP") (pintype "input"))
      (node (ref "CANL_4_C4") (pin "TP") (pinfunction "TP_TP") (pintype "input"))
      (node (ref "X2") (pin "3") (pinfunction "1_3") (pintype "passive"))
    )
    (net (code "11") (name "/CAN_RX") (class "Default")
      (node (ref "U$1") (pin "4") (pinfunction "R_4") (pintype "bidirectional"))
      (node (ref "U1") (pin "27") (pinfunction "P4.0/SCB0:SCL1_27") (pintype "bidirectional"))
    )
    (net (code "12") (name "/CAN_TX") (class "Default")
      (node (ref "U$1") (pin "1") (pinfunction "D_1") (pintype "bidirectional"))
      (node (ref "U1") (pin "28") (pinfunction "P4.1/SCB0:SDA1_28") (pintype "bidirectional"))
    )
    (net (code "13") (name "/CMOD") (class "Default")
      (node (ref "C4") (pin "1") (pinfunction "1_1") (pintype "passive"))
      (node (ref "R18") (pin "2") (pinfunction "2_2") (pintype "passive"))
      (node (ref "U1") (pin "29") (pinfunction "P4.2_29") (pintype "bidirectional"))
    )
    (net (code "14") (name "/CTANK") (class "Default")
      (node (ref "C5") (pin "1") (pinfunction "1_1") (pintype "passive"))
      (node (ref "U1") (pin "30") (pinfunction "P4.3_30") (pintype "bidirectional"))
    )
    (net (code "15") (name "/LED_S1") (class "Default")
      (node (ref "LED1") (pin "A") (pinfunction "A_A") (pintype "passive"))
      (node (ref "U1") (pin "4") (pinfunction "P2.2_4") (pintype "bidirectional"))
    )
    (net (code "16") (name "/LED_S2") (class "Default")
      (node (ref "L_C2") (pin "TP") (pinfunction "TP_TP") (pintype "input"))
      (node (ref "U1") (pin "5") (pinfunction "P2.3_5") (pintype "bidirectional"))
    )
    (net (code "17") (name "/LED_S2_C2") (class "Default")
      (node (ref "LED2") (pin "A") (pinfunction "A_A") (pintype "passive"))
      (node (ref "L_C2_C1") (pin "TP") (pinfunction "TP_TP") (pintype "input"))
    )
    (net (code "18") (name "/LED_S3") (class "Default")
      (node (ref "L_C3") (pin "TP") (pinfunction "TP_TP") (pintype "input"))
      (node (ref "U1") (pin "6") (pinfunction "P2.4_6") (pintype "bidirectional"))
    )
    (net (code "19") (name "/LED_S3_C3") (class "Default")
      (node (ref "LED3") (pin "A") (pinfunction "A_A") (pintype "passive"))
      (node (ref "L_C2_C3") (pin "TP") (pinfunction "TP_TP") (pintype "input"))
    )
    (net (code "20") (name "/LED_S4") (class "Default")
      (node (ref "L_C4") (pin "TP") (pinfunction "TP_TP") (pintype "input"))
      (node (ref "U1") (pin "7") (pinfunction "P2.5_7") (pintype "bidirectional"))
    )
    (net (code "21") (name "/LED_S4_C4") (class "Default")
      (node (ref "LED4") (pin "A") (pinfunction "A_A") (pintype "passive"))
      (node (ref "X2") (pin "9") (pinfunction "1_9") (pintype "passive"))
    )
    (net (code "22") (name "/LED_T_S4") (class "Default")
      (node (ref "L_C2_C4") (pin "TP") (pinfunction "TP_TP") (pintype "input"))
      (node (ref "X1") (pin "9") (pinfunction "1_9") (pintype "passive"))
    )
    (net (code "23") (name "/MOTOR") (class "Default")
      (node (ref "S1") (pin "3") (pinfunction "3_3") (pintype "passive"))
      (node (ref "U1") (pin "8") (pinfunction "P2.6_8") (pintype "bidirectional"))
      (node (ref "U1") (pin "9") (pinfunction "P2.7_9") (pintype "bidirectional"))
    )
    (net (code "24") (name "/P0_1") (class "Default")
      (node (ref "R11") (pin "1") (pinfunction "1_1") (pintype "passive"))
      (node (ref "U1") (pin "40") (pinfunction "P0.1/CAN1TX_40") (pintype "bidirectional"))
    )
    (net (code "25") (name "/P0_4") (class "Default")
      (node (ref "C8") (pin "1") (pinfunction "1_1") (pintype "passive"))
      (node (ref "CRYSTAL") (pin "2") (pinfunction "2_2") (pintype "passive"))
      (node (ref "U1") (pin "43") (pinfunction "P0.4_43") (pintype "bidirectional"))
    )
    (net (code "26") (name "/P0_5") (class "Default")
      (node (ref "C9") (pin "1") (pinfunction "1_1") (pintype "passive"))
      (node (ref "CRYSTAL") (pin "1") (pinfunction "1_1") (pintype "passive"))
      (node (ref "U1") (pin "44") (pinfunction "P0.5_44") (pintype "bidirectional"))
    )
    (net (code "27") (name "/SAR_BY") (class "Default")
      (node (ref "C6") (pin "1") (pinfunction "1_1") (pintype "passive"))
      (node (ref "U1") (pin "1") (pinfunction "P1.7/VREF_1") (pintype "bidirectional"))
    )
    (net (code "28") (name "/SCL_S1") (class "Default")
      (node (ref "R8") (pin "2") (pinfunction "2_2") (pintype "passive"))
      (node (ref "U1") (pin "2") (pinfunction "P2.0/SCB1:SCL1_2") (pintype "bidirectional"))
      (node (ref "U2") (pin "5") (pinfunction "SCL_5") (pintype "input"))
    )
    (net (code "29") (name "/SCL_S2") (class "Default")
      (node (ref "SCL_S2_C2") (pin "TP") (pinfunction "TP_TP") (pintype "input"))
      (node (ref "U1") (pin "51") (pinfunction "P5.0_51") (pintype "bidirectional"))
    )
    (net (code "30") (name "/SCL_S2_U") (class "Default")
      (node (ref "R10") (pin "2") (pinfunction "2_2") (pintype "passive"))
      (node (ref "SCL_S2_C2_C1") (pin "TP") (pinfunction "TP_TP") (pintype "input"))
      (node (ref "U3") (pin "5") (pinfunction "SCL_5") (pintype "input"))
    )
    (net (code "31") (name "/SCL_S3") (class "Default")
      (node (ref "SCL_S3_C3") (pin "TP") (pinfunction "TP_TP") (pintype "input"))
      (node (ref "U1") (pin "12") (pinfunction "P6.0/CAN0TX_EN_12") (pintype "bidirectional"))
    )
    (net (code "32") (name "/SCL_S3_U") (class "Default")
      (node (ref "R27") (pin "1") (pinfunction "1_1") (pintype "passive"))
      (node (ref "SCL_S3_C3_C2") (pin "TP") (pinfunction "TP_TP") (pintype "input"))
      (node (ref "U4") (pin "5") (pinfunction "SCL_5") (pintype "input"))
    )
    (net (code "33") (name "/SCL_S4") (class "Default")
      (node (ref "SCL_S4_C4") (pin "TP") (pinfunction "TP_TP") (pintype "input"))
      (node (ref "U1") (pin "58") (pinfunction "P1.0_58") (pintype "bidirectional"))
    )
    (net (code "34") (name "/SCL_S4_U") (class "Default")
      (node (ref "SCL_S4_C4_C2") (pin "TP") (pinfunction "TP_TP") (pintype "input"))
      (node (ref "X1") (pin "7") (pinfunction "1_7") (pintype "passive"))
    )
    (net (code "35") (name "/SCL_S4_U_1") (class "Default")
      (node (ref "R25") (pin "1") (pinfunction "1_1") (pintype "passive"))
      (node (ref "U5") (pin "5") (pinfunction "SCL_5") (pintype "input"))
      (node (ref "X2") (pin "7") (pinfunction "1_7") (pintype "passive"))
    )
    (net (code "36") (name "/SDA_S1") (class "Default")
      (node (ref "R6") (pin "2") (pinfunction "2_2") (pintype "passive"))
      (node (ref "U1") (pin "3") (pinfunction "P2.1/SCB1:SDA1_3") (pintype "bidirectional"))
      (node (ref "U2") (pin "4") (pinfunction "SDA_4") (pintype "bidirectional"))
    )
    (net (code "37") (name "/SDA_S2") (class "Default")
      (node (ref "SDA_S2_C1") (pin "TP") (pinfunction "TP_TP") (pintype "input"))
      (node (ref "U1") (pin "52") (pinfunction "P5.1_52") (pintype "bidirectional"))
    )
    (net (code "38") (name "/SDA_S2_U") (class "Default")
      (node (ref "R12") (pin "2") (pinfunction "2_2") (pintype "passive"))
      (node (ref "SDA_S2_C2_C2") (pin "TP") (pinfunction "TP_TP") (pintype "input"))
      (node (ref "U3") (pin "4") (pinfunction "SDA_4") (pintype "bidirectional"))
    )
    (net (code "39") (name "/SDA_S3") (class "Default")
      (node (ref "SDA_S3_C1") (pin "TP") (pinfunction "TP_TP") (pintype "input"))
      (node (ref "U1") (pin "13") (pinfunction "P6.1/CAN0RX_13") (pintype "bidirectional"))
    )
    (net (code "40") (name "/SDA_S3_U") (class "Default")
      (node (ref "R26") (pin "1") (pinfunction "1_1") (pintype "passive"))
      (node (ref "SDA_S3_C3_C4") (pin "TP") (pinfunction "TP_TP") (pintype "input"))
      (node (ref "U4") (pin "4") (pinfunction "SDA_4") (pintype "bidirectional"))
    )
    (net (code "41") (name "/SDA_S4") (class "Default")
      (node (ref "SDA_S4_C1") (pin "TP") (pinfunction "TP_TP") (pintype "input"))
      (node (ref "U1") (pin "59") (pinfunction "P1.1_59") (pintype "bidirectional"))
    )
    (net (code "42") (name "/SDA_S4_U") (class "Default")
      (node (ref "SDA_S4_C4_C4") (pin "TP") (pinfunction "TP_TP") (pintype "input"))
      (node (ref "X1") (pin "8") (pinfunction "1_8") (pintype "passive"))
    )
    (net (code "43") (name "/SDA_S4_U_1") (class "Default")
      (node (ref "R24") (pin "1") (pinfunction "1_1") (pintype "passive"))
      (node (ref "U5") (pin "4") (pinfunction "SDA_4") (pintype "bidirectional"))
      (node (ref "X2") (pin "8") (pinfunction "1_8") (pintype "passive"))
    )
    (net (code "44") (name "/SWDCLK") (class "Default")
      (node (ref "R2") (pin "2") (pinfunction "2_2") (pintype "passive"))
      (node (ref "U1") (pin "21") (pinfunction "P3.3_21") (pintype "bidirectional"))
    )
    (net (code "45") (name "/SWDIO") (class "Default")
      (node (ref "R3") (pin "2") (pinfunction "2_2") (pintype "passive"))
      (node (ref "U1") (pin "20") (pinfunction "P3.2_20") (pintype "bidirectional"))
    )
    (net (code "46") (name "/UART_RX") (class "Default")
      (node (ref "U1") (pin "37") (pinfunction "P7.0/SCB3:SCL1_37") (pintype "bidirectional"))
    )
    (net (code "47") (name "/UART_TX") (class "Default")
      (node (ref "U1") (pin "38") (pinfunction "P7.1/SCB3:SDA1_38") (pintype "bidirectional"))
    )
    (net (code "48") (name "/VCCD") (class "Default")
      (node (ref "C7") (pin "1") (pinfunction "1_1") (pintype "passive"))
      (node (ref "U1") (pin "48") (pinfunction "VCCD_48") (pintype "bidirectional"))
    )
    (net (code "49") (name "/VCC_C2") (class "Default")
      (node (ref "DINA") (pin "2") (pinfunction "2_2") (pintype "passive"))
      (node (ref "IC1") (pin "3") (pinfunction "IN_3") (pintype "input"))
      (node (ref "VCC_1_C2") (pin "TP") (pinfunction "TP_TP") (pintype "input"))
      (node (ref "VCC_2_C2") (pin "TP") (pinfunction "TP_TP") (pintype "input"))
      (node (ref "VCC_3_C2") (pin "TP") (pinfunction "TP_TP") (pintype "input"))
      (node (ref "VCC_4_C2") (pin "TP") (pinfunction "TP_TP") (pintype "input"))
      (node (ref "VCC_C2") (pin "TP") (pinfunction "TP_TP") (pintype "input"))
      (node (ref "VCC_C2_C3") (pin "TP") (pinfunction "TP_TP") (pintype "input"))
    )
    (net (code "50") (name "/VCC_C3") (class "Default")
      (node (ref "VCC_1_C3") (pin "TP") (pinfunction "TP_TP") (pintype "input"))
      (node (ref "VCC_2_C3") (pin "TP") (pinfunction "TP_TP") (pintype "input"))
      (node (ref "VCC_3_C3") (pin "TP") (pinfunction "TP_TP") (pintype "input"))
      (node (ref "VCC_4_C3") (pin "TP") (pinfunction "TP_TP") (pintype "input"))
      (node (ref "VCC_C3") (pin "TP") (pinfunction "TP_TP") (pintype "input"))
      (node (ref "X1") (pin "1") (pinfunction "1_1") (pintype "passive"))
      (node (ref "X1") (pin "10") (pinfunction "1_10") (pintype "passive"))
    )
    (net (code "51") (name "/VCC_C4") (class "Default")
      (node (ref "VCC_1_C4") (pin "TP") (pinfunction "TP_TP") (pintype "input"))
      (node (ref "VCC_2_C4") (pin "TP") (pinfunction "TP_TP") (pintype "input"))
      (node (ref "VCC_3_C4") (pin "TP") (pinfunction "TP_TP") (pintype "input"))
      (node (ref "VCC_4_C4") (pin "TP") (pinfunction "TP_TP") (pintype "input"))
      (node (ref "VCC_REINFORCEMENT") (pin "TP") (pinfunction "TP_TP") (pintype "input"))
      (node (ref "X2") (pin "1") (pinfunction "1_1") (pintype "passive"))
      (node (ref "X2") (pin "10") (pinfunction "1_10") (pintype "passive"))
    )
    (net (code "52") (name "/VDDA") (class "Default")
      (node (ref "U1") (pin "11") (pinfunction "VDDA1_11") (pintype "bidirectional"))
      (node (ref "U1") (pin "56") (pinfunction "VDDA2_56") (pintype "bidirectional"))
      (node (ref "VDDA_C1") (pin "TP") (pinfunction "TP_TP") (pintype "input"))
    )
    (net (code "53") (name "/VDDA2") (class "Default")
      (node (ref "L1") (pin "2") (pinfunction "2_2") (pintype "passive"))
      (node (ref "VDDA_C2") (pin "TP") (pinfunction "TP_TP") (pintype "input"))
    )
    (net (code "54") (name "/VDDD") (class "Default")
      (node (ref "U1") (pin "50") (pinfunction "VDDD_50") (pintype "bidirectional"))
      (node (ref "VDDD_C1") (pin "TP") (pinfunction "TP_TP") (pintype "input"))
    )
    (net (code "55") (name "/VDDD2") (class "Default")
      (node (ref "L2") (pin "2") (pinfunction "2_2") (pintype "passive"))
      (node (ref "VDDD_C2") (pin "TP") (pinfunction "TP_TP") (pintype "input"))
    )
    (net (code "56") (name "/VDDIO") (class "Default")
      (node (ref "U1") (pin "26") (pinfunction "VDDIO_26") (pintype "bidirectional"))
      (node (ref "VDDIO_C1") (pin "TP") (pinfunction "TP_TP") (pintype "input"))
    )
    (net (code "57") (name "/VDDIO2") (class "Default")
      (node (ref "R15") (pin "2") (pinfunction "2_2") (pintype "passive"))
      (node (ref "VDDIO_C2") (pin "TP") (pinfunction "TP_TP") (pintype "input"))
    )
    (net (code "58") (name "/XRES") (class "Default")
      (node (ref "C10") (pin "1") (pinfunction "1_1") (pintype "passive"))
      (node (ref "R1") (pin "2") (pinfunction "2_2") (pintype "passive"))
      (node (ref "R14") (pin "2") (pinfunction "2_2") (pintype "passive"))
      (node (ref "U1") (pin "47") (pinfunction "XRES_47") (pintype "bidirectional"))
    )
    (net (code "59") (name "GND1") (class "Default")
      (node (ref "C10") (pin "2") (pinfunction "2_2") (pintype "passive"))
      (node (ref "C4") (pin "2") (pinfunction "2_2") (pintype "passive"))
      (node (ref "C5") (pin "2") (pinfunction "2_2") (pintype "passive"))
      (node (ref "C6") (pin "2") (pinfunction "2_2") (pintype "passive"))
      (node (ref "C7") (pin "2") (pinfunction "2_2") (pintype "passive"))
      (node (ref "C8") (pin "2") (pinfunction "2_2") (pintype "passive"))
      (node (ref "C9") (pin "2") (pinfunction "2_2") (pintype "passive"))
      (node (ref "CN1") (pin "D-") (pinfunction "D-_D-") (pintype "bidirectional"))
      (node (ref "GND_1_C1") (pin "TP") (pinfunction "TP_TP") (pintype "input"))
      (node (ref "GND_2_C1") (pin "TP") (pinfunction "TP_TP") (pintype "input"))
      (node (ref "GND_3_C1") (pin "TP") (pinfunction "TP_TP") (pintype "input"))
      (node (ref "GND_4_C1") (pin "TP") (pinfunction "TP_TP") (pintype "input"))
      (node (ref "GND_C1") (pin "TP") (pinfunction "TP_TP") (pintype "input"))
      (node (ref "R13") (pin "1") (pinfunction "1_1") (pintype "passive"))
      (node (ref "R17") (pin "2") (pinfunction "2_2") (pintype "passive"))
      (node (ref "R18") (pin "1") (pinfunction "1_1") (pintype "passive"))
      (node (ref "R19") (pin "2") (pinfunction "2_2") (pintype "passive"))
      (node (ref "R4") (pin "2") (pinfunction "2_2") (pintype "passive"))
      (node (ref "U$1") (pin "2") (pinfunction "GND_2") (pintype "power_in"))
      (node (ref "U1") (pin "10") (pinfunction "VSSA1_10") (pintype "bidirectional"))
      (node (ref "U1") (pin "17") (pinfunction "VSSIO_17") (pintype "bidirectional"))
      (node (ref "U1") (pin "49") (pinfunction "VSSD_49") (pintype "bidirectional"))
      (node (ref "U1") (pin "57") (pinfunction "VSSA2_57") (pintype "bidirectional"))
      (node (ref "U2") (pin "12") (pinfunction "GND_12") (pintype "power_in"))
      (node (ref "U2") (pin "13") (pinfunction "GND_13") (pintype "power_in"))
    )
    (net (code "60") (name "GND2") (class "Default")
      (node (ref "DINA") (pin "3") (pinfunction "3_3") (pintype "passive"))
      (node (ref "GND_1_C2") (pin "TP") (pinfunction "TP_TP") (pintype "input"))
      (node (ref "GND_2_C2") (pin "TP") (pinfunction "TP_TP") (pintype "input"))
      (node (ref "GND_3_C2") (pin "TP") (pinfunction "TP_TP") (pintype "input"))
      (node (ref "GND_4_C2") (pin "TP") (pinfunction "TP_TP") (pintype "input"))
      (node (ref "GND_C2") (pin "TP") (pinfunction "TP_TP") (pintype "input"))
      (node (ref "GND_C2_C3") (pin "TP") (pinfunction "TP_TP") (pintype "input"))
      (node (ref "IC1") (pin "1") (pinfunction "ADJ_1") (pintype "input"))
      (node (ref "R20") (pin "2") (pinfunction "2_2") (pintype "passive"))
      (node (ref "R23") (pin "2") (pinfunction "2_2") (pintype "passive"))
      (node (ref "R5") (pin "1") (pinfunction "1_1") (pintype "passive"))
      (node (ref "U3") (pin "12") (pinfunction "GND_12") (pintype "power_in"))
      (node (ref "U3") (pin "13") (pinfunction "GND_13") (pintype "power_in"))
    )
    (net (code "61") (name "GND3") (class "Default")
      (node (ref "GND_1_C3") (pin "TP") (pinfunction "TP_TP") (pintype "input"))
      (node (ref "GND_2_C3") (pin "TP") (pinfunction "TP_TP") (pintype "input"))
      (node (ref "GND_3_C3") (pin "TP") (pinfunction "TP_TP") (pintype "input"))
      (node (ref "GND_4_C3") (pin "TP") (pinfunction "TP_TP") (pintype "input"))
      (node (ref "GND_C3") (pin "TP") (pinfunction "TP_TP") (pintype "input"))
      (node (ref "R21") (pin "2") (pinfunction "2_2") (pintype "passive"))
      (node (ref "R7") (pin "1") (pinfunction "1_1") (pintype "passive"))
      (node (ref "U4") (pin "12") (pinfunction "GND_12") (pintype "power_in"))
      (node (ref "U4") (pin "13") (pinfunction "GND_13") (pintype "power_in"))
      (node (ref "X1") (pin "2") (pinfunction "1_2") (pintype "passive"))
      (node (ref "X1") (pin "6") (pinfunction "1_6") (pintype "passive"))
    )
    (net (code "62") (name "GND4") (class "Default")
      (node (ref "GND_1_C4") (pin "TP") (pinfunction "TP_TP") (pintype "input"))
      (node (ref "GND_2_C4") (pin "TP") (pinfunction "TP_TP") (pintype "input"))
      (node (ref "GND_3_C4") (pin "TP") (pinfunction "TP_TP") (pintype "input"))
      (node (ref "GND_4_C4") (pin "TP") (pinfunction "TP_TP") (pintype "input"))
      (node (ref "GND_REINFORCEMENT") (pin "TP") (pinfunction "TP_TP") (pintype "input"))
      (node (ref "R22") (pin "2") (pinfunction "2_2") (pintype "passive"))
      (node (ref "R9") (pin "1") (pinfunction "1_1") (pintype "passive"))
      (node (ref "U5") (pin "12") (pinfunction "GND_12") (pintype "power_in"))
      (node (ref "U5") (pin "13") (pinfunction "GND_13") (pintype "power_in"))
      (node (ref "X2") (pin "2") (pinfunction "1_2") (pintype "passive"))
      (node (ref "X2") (pin "6") (pinfunction "1_6") (pintype "passive"))
    )
    (net (code "63") (name "Net-(CANH_1_C2-PadTP)") (class "Default")
      (node (ref "CANH_1_C2") (pin "TP") (pinfunction "TP_TP") (pintype "input"))
      (node (ref "CANH_2_C2") (pin "TP") (pinfunction "TP_TP") (pintype "input"))
      (node (ref "CANH_3_C2") (pin "TP") (pinfunction "TP_TP") (pintype "input"))
      (node (ref "CANH_4_C2") (pin "TP") (pinfunction "TP_TP") (pintype "input"))
      (node (ref "CANH_C2") (pin "TP") (pinfunction "TP_TP") (pintype "input"))
      (node (ref "CANH_C2_C3") (pin "TP") (pinfunction "TP_TP") (pintype "input"))
    )
    (net (code "64") (name "Net-(CANL_1_C2-PadTP)") (class "Default")
      (node (ref "CANL_1_C2") (pin "TP") (pinfunction "TP_TP") (pintype "input"))
      (node (ref "CANL_2_C2") (pin "TP") (pinfunction "TP_TP") (pintype "input"))
      (node (ref "CANL_3_C2") (pin "TP") (pinfunction "TP_TP") (pintype "input"))
      (node (ref "CANL_4_C2") (pin "TP") (pinfunction "TP_TP") (pintype "input"))
      (node (ref "CANL_C2") (pin "TP") (pinfunction "TP_TP") (pintype "input"))
      (node (ref "CANL_C2_C3") (pin "TP") (pinfunction "TP_TP") (pintype "input"))
    )
    (net (code "65") (name "Net-(CN1-PadD+)") (class "Default")
      (node (ref "CN1") (pin "D+") (pinfunction "D+_D+") (pintype "bidirectional"))
      (node (ref "R1") (pin "1") (pinfunction "1_1") (pintype "passive"))
    )
    (net (code "66") (name "Net-(CN1-PadGND)") (class "Default")
      (node (ref "CN1") (pin "GND") (pinfunction "GND_GND") (pintype "power_in"))
      (node (ref "R3") (pin "1") (pinfunction "1_1") (pintype "passive"))
    )
    (net (code "67") (name "Net-(CN1-PadID)") (class "Default")
      (node (ref "CN1") (pin "ID") (pinfunction "ID_ID") (pintype "bidirectional"))
      (node (ref "R2") (pin "1") (pinfunction "1_1") (pintype "passive"))
    )
    (net (code "68") (name "Net-(DINA-Pad1)") (class "Default")
      (node (ref "DINA") (pin "1") (pinfunction "1_1") (pintype "passive"))
      (node (ref "DN_C2") (pin "TP") (pinfunction "TP_TP") (pintype "input"))
    )
    (net (code "69") (name "Net-(DN_C1-PadTP)") (class "Default")
      (node (ref "DN_C1") (pin "TP") (pinfunction "TP_TP") (pintype "input"))
      (node (ref "S1") (pin "2") (pinfunction "2_2") (pintype "passive"))
    )
    (net (code "70") (name "Net-(LED1-PadC)") (class "Default")
      (node (ref "LED1") (pin "C") (pinfunction "C_C") (pintype "passive"))
      (node (ref "R19") (pin "1") (pinfunction "1_1") (pintype "passive"))
    )
    (net (code "71") (name "Net-(LED2-PadC)") (class "Default")
      (node (ref "LED2") (pin "C") (pinfunction "C_C") (pintype "passive"))
      (node (ref "R20") (pin "1") (pinfunction "1_1") (pintype "passive"))
    )
    (net (code "72") (name "Net-(LED3-PadC)") (class "Default")
      (node (ref "LED3") (pin "C") (pinfunction "C_C") (pintype "passive"))
      (node (ref "R21") (pin "1") (pinfunction "1_1") (pintype "passive"))
    )
    (net (code "73") (name "Net-(LED4-PadC)") (class "Default")
      (node (ref "LED4") (pin "C") (pinfunction "C_C") (pintype "passive"))
      (node (ref "R22") (pin "1") (pinfunction "1_1") (pintype "passive"))
    )
    (net (code "74") (name "Net-(LED5-PadC)") (class "Default")
      (node (ref "LED5") (pin "C") (pinfunction "C_C") (pintype "passive"))
      (node (ref "R23") (pin "1") (pinfunction "1_1") (pintype "passive"))
    )
    (net (code "75") (name "Net-(L_C1_C3-PadTP)") (class "Default")
      (node (ref "L_C1_C3") (pin "TP") (pinfunction "TP_TP") (pintype "input"))
      (node (ref "L_C3_C2") (pin "TP") (pinfunction "TP_TP") (pintype "input"))
    )
    (net (code "76") (name "Net-(L_C1_C4-PadTP)") (class "Default")
      (node (ref "L_C1_C4") (pin "TP") (pinfunction "TP_TP") (pintype "input"))
      (node (ref "L_C4_C1") (pin "TP") (pinfunction "TP_TP") (pintype "input"))
    )
    (net (code "77") (name "Net-(R4-Pad1)") (class "Default")
      (node (ref "R4") (pin "1") (pinfunction "1_1") (pintype "passive"))
      (node (ref "U2") (pin "2") (pinfunction "IR_CA_2") (pintype "power_in"))
      (node (ref "U2") (pin "3") (pinfunction "IR_CA_3") (pintype "power_in"))
    )
    (net (code "78") (name "Net-(R5-Pad2)") (class "Default")
      (node (ref "R5") (pin "2") (pinfunction "2_2") (pintype "passive"))
      (node (ref "U3") (pin "2") (pinfunction "IR_CA_2") (pintype "power_in"))
      (node (ref "U3") (pin "3") (pinfunction "IR_CA_3") (pintype "power_in"))
    )
    (net (code "79") (name "Net-(R7-Pad2)") (class "Default")
      (node (ref "R7") (pin "2") (pinfunction "2_2") (pintype "passive"))
      (node (ref "U4") (pin "2") (pinfunction "IR_CA_2") (pintype "power_in"))
      (node (ref "U4") (pin "3") (pinfunction "IR_CA_3") (pintype "power_in"))
    )
    (net (code "80") (name "Net-(R9-Pad2)") (class "Default")
      (node (ref "R9") (pin "2") (pinfunction "2_2") (pintype "passive"))
      (node (ref "U5") (pin "2") (pinfunction "IR_CA_2") (pintype "power_in"))
      (node (ref "U5") (pin "3") (pinfunction "IR_CA_3") (pintype "power_in"))
    )
    (net (code "81") (name "Net-(R11-Pad2)") (class "Default")
      (node (ref "R11") (pin "2") (pinfunction "2_2") (pintype "passive"))
      (node (ref "R13") (pin "2") (pinfunction "2_2") (pintype "passive"))
    )
    (net (code "82") (name "Net-(SCL_S3_C1_C3-PadTP)") (class "Default")
      (node (ref "SCL_S3_C1_C3") (pin "TP") (pinfunction "TP_TP") (pintype "input"))
      (node (ref "SCL_S3_C3_C1") (pin "TP") (pinfunction "TP_TP") (pintype "input"))
    )
    (net (code "83") (name "Net-(SCL_S4_C1_C4-PadTP)") (class "Default")
      (node (ref "SCL_S4_C1_C4") (pin "TP") (pinfunction "TP_TP") (pintype "input"))
      (node (ref "SCL_S4_C4_C1") (pin "TP") (pinfunction "TP_TP") (pintype "input"))
    )
    (net (code "84") (name "Net-(SDA_S3_C1_C1-PadTP)") (class "Default")
      (node (ref "SDA_S3_C1_C1") (pin "TP") (pinfunction "TP_TP") (pintype "input"))
      (node (ref "SDA_S3_C3_C3") (pin "TP") (pinfunction "TP_TP") (pintype "input"))
    )
    (net (code "85") (name "Net-(SDA_S4_C1_C1-PadTP)") (class "Default")
      (node (ref "SDA_S4_C1_C1") (pin "TP") (pinfunction "TP_TP") (pintype "input"))
      (node (ref "SDA_S4_C4_C3") (pin "TP") (pinfunction "TP_TP") (pintype "input"))
    )
    (net (code "86") (name "Net-(U$1-CANH)") (class "Default")
      (node (ref "R16") (pin "2") (pinfunction "2_2") (pintype "passive"))
      (node (ref "S1") (pin "4") (pinfunction "4_4") (pintype "passive"))
      (node (ref "U$1") (pin "7") (pinfunction "CANH_7") (pintype "bidirectional"))
    )
    (net (code "87") (name "Net-(U$1-RS)") (class "Default")
      (node (ref "R17") (pin "1") (pinfunction "1_1") (pintype "passive"))
      (node (ref "U$1") (pin "8") (pinfunction "RS_8") (pintype "bidirectional"))
    )
    (net (code "88") (name "Net-(VCC_1_C1-PadTP)") (class "Default")
      (node (ref "VCC_1_C1") (pin "TP") (pinfunction "TP_TP") (pintype "input"))
      (node (ref "VCC_2_C1") (pin "TP") (pinfunction "TP_TP") (pintype "input"))
      (node (ref "VCC_3_C1") (pin "TP") (pinfunction "TP_TP") (pintype "input"))
      (node (ref "VCC_4_C1") (pin "TP") (pinfunction "TP_TP") (pintype "input"))
      (node (ref "VCC_C1") (pin "TP") (pinfunction "TP_TP") (pintype "input"))
    )
    (net (code "89") (name "unconnected-(MECH_LINK_1-PadTP)") (class "Default")
      (node (ref "MECH_LINK_1") (pin "TP") (pinfunction "TP_TP") (pintype "input"))
    )
    (net (code "90") (name "unconnected-(MECH_LINK_2-PadTP)") (class "Default")
      (node (ref "MECH_LINK_2") (pin "TP") (pinfunction "TP_TP") (pintype "input"))
    )
    (net (code "91") (name "unconnected-(MECH_LINK_3-PadTP)") (class "Default")
      (node (ref "MECH_LINK_3") (pin "TP") (pinfunction "TP_TP") (pintype "input"))
    )
    (net (code "92") (name "unconnected-(MECH_LINK_4-PadTP)") (class "Default")
      (node (ref "MECH_LINK_4") (pin "TP") (pinfunction "TP_TP") (pintype "input"))
    )
    (net (code "93") (name "unconnected-(MECH_LINK_5-PadTP)") (class "Default")
      (node (ref "MECH_LINK_5") (pin "TP") (pinfunction "TP_TP") (pintype "input"))
    )
    (net (code "94") (name "unconnected-(MECH_LINK_6-PadTP)") (class "Default")
      (node (ref "MECH_LINK_6") (pin "TP") (pinfunction "TP_TP") (pintype "input"))
    )
    (net (code "95") (name "unconnected-(MECH_LINK_7-PadTP)") (class "Default")
      (node (ref "MECH_LINK_7") (pin "TP") (pinfunction "TP_TP") (pintype "input"))
    )
    (net (code "96") (name "unconnected-(MECH_LINK_8-PadTP)") (class "Default")
      (node (ref "MECH_LINK_8") (pin "TP") (pinfunction "TP_TP") (pintype "input"))
    )
    (net (code "97") (name "unconnected-(MECH_LINK_9-PadTP)") (class "Default")
      (node (ref "MECH_LINK_9") (pin "TP") (pinfunction "TP_TP") (pintype "input"))
    )
    (net (code "98") (name "unconnected-(MECH_LINK_11-PadTP)") (class "Default")
      (node (ref "MECH_LINK_11") (pin "TP") (pinfunction "TP_TP") (pintype "input"))
    )
    (net (code "99") (name "unconnected-(U$1-VREF-Pad5)") (class "Default")
      (node (ref "U$1") (pin "5") (pinfunction "VREF_5") (pintype "bidirectional"))
    )
    (net (code "100") (name "unconnected-(U1-NC1-Pad34)") (class "Default")
      (node (ref "U1") (pin "34") (pinfunction "NC1_34") (pintype "bidirectional"))
    )
    (net (code "101") (name "unconnected-(U1-NC2-Pad35)") (class "Default")
      (node (ref "U1") (pin "35") (pinfunction "NC2_35") (pintype "bidirectional"))
    )
    (net (code "102") (name "unconnected-(U1-NC3-Pad36)") (class "Default")
      (node (ref "U1") (pin "36") (pinfunction "NC3_36") (pintype "bidirectional"))
    )
    (net (code "103") (name "unconnected-(U1-P0.0{slash}CAN1RX-Pad39)") (class "Default")
      (node (ref "U1") (pin "39") (pinfunction "P0.0/CAN1RX_39") (pintype "bidirectional"))
    )
    (net (code "104") (name "unconnected-(U1-P0.2-Pad41)") (class "Default")
      (node (ref "U1") (pin "41") (pinfunction "P0.2_41") (pintype "bidirectional"))
    )
    (net (code "105") (name "unconnected-(U1-P0.3-Pad42)") (class "Default")
      (node (ref "U1") (pin "42") (pinfunction "P0.3_42") (pintype "bidirectional"))
    )
    (net (code "106") (name "unconnected-(U1-P0.6-Pad45)") (class "Default")
      (node (ref "U1") (pin "45") (pinfunction "P0.6_45") (pintype "bidirectional"))
    )
    (net (code "107") (name "unconnected-(U1-P0.7{slash}CAN1TX_EN-Pad46)") (class "Default")
      (node (ref "U1") (pin "46") (pinfunction "P0.7/CAN1TX_EN_46") (pintype "bidirectional"))
    )
    (net (code "108") (name "unconnected-(U1-P1.2-Pad60)") (class "Default")
      (node (ref "U1") (pin "60") (pinfunction "P1.2_60") (pintype "bidirectional"))
    )
    (net (code "109") (name "unconnected-(U1-P1.3-Pad61)") (class "Default")
      (node (ref "U1") (pin "61") (pinfunction "P1.3_61") (pintype "bidirectional"))
    )
    (net (code "110") (name "unconnected-(U1-P1.4-Pad62)") (class "Default")
      (node (ref "U1") (pin "62") (pinfunction "P1.4_62") (pintype "bidirectional"))
    )
    (net (code "111") (name "unconnected-(U1-P1.5-Pad63)") (class "Default")
      (node (ref "U1") (pin "63") (pinfunction "P1.5_63") (pintype "bidirectional"))
    )
    (net (code "112") (name "unconnected-(U1-P1.6-Pad64)") (class "Default")
      (node (ref "U1") (pin "64") (pinfunction "P1.6_64") (pintype "bidirectional"))
    )
    (net (code "113") (name "unconnected-(U1-P3.0{slash}SCB1:RX-Pad18)") (class "Default")
      (node (ref "U1") (pin "18") (pinfunction "P3.0/SCB1:RX_18") (pintype "bidirectional"))
    )
    (net (code "114") (name "unconnected-(U1-P3.1{slash}SCB1:TX-Pad19)") (class "Default")
      (node (ref "U1") (pin "19") (pinfunction "P3.1/SCB1:TX_19") (pintype "bidirectional"))
    )
    (net (code "115") (name "unconnected-(U1-P3.4-Pad22)") (class "Default")
      (node (ref "U1") (pin "22") (pinfunction "P3.4_22") (pintype "bidirectional"))
    )
    (net (code "116") (name "unconnected-(U1-P3.5-Pad23)") (class "Default")
      (node (ref "U1") (pin "23") (pinfunction "P3.5_23") (pintype "bidirectional"))
    )
    (net (code "117") (name "unconnected-(U1-P3.6-Pad24)") (class "Default")
      (node (ref "U1") (pin "24") (pinfunction "P3.6_24") (pintype "bidirectional"))
    )
    (net (code "118") (name "unconnected-(U1-P3.7-Pad25)") (class "Default")
      (node (ref "U1") (pin "25") (pinfunction "P3.7_25") (pintype "bidirectional"))
    )
    (net (code "119") (name "unconnected-(U1-P4.4-Pad31)") (class "Default")
      (node (ref "U1") (pin "31") (pinfunction "P4.4_31") (pintype "bidirectional"))
    )
    (net (code "120") (name "unconnected-(U1-P4.5-Pad32)") (class "Default")
      (node (ref "U1") (pin "32") (pinfunction "P4.5_32") (pintype "bidirectional"))
    )
    (net (code "121") (name "unconnected-(U1-P4.6-Pad33)") (class "Default")
      (node (ref "U1") (pin "33") (pinfunction "P4.6_33") (pintype "bidirectional"))
    )
    (net (code "122") (name "unconnected-(U1-P5.2-Pad53)") (class "Default")
      (node (ref "U1") (pin "53") (pinfunction "P5.2_53") (pintype "bidirectional"))
    )
    (net (code "123") (name "unconnected-(U1-P5.3-Pad54)") (class "Default")
      (node (ref "U1") (pin "54") (pinfunction "P5.3_54") (pintype "bidirectional"))
    )
    (net (code "124") (name "unconnected-(U1-P5.5-Pad55)") (class "Default")
      (node (ref "U1") (pin "55") (pinfunction "P5.5_55") (pintype "bidirectional"))
    )
    (net (code "125") (name "unconnected-(U1-P6.2{slash}CAN0TX-Pad14)") (class "Default")
      (node (ref "U1") (pin "14") (pinfunction "P6.2/CAN0TX_14") (pintype "bidirectional"))
    )
    (net (code "126") (name "unconnected-(U1-P6.4-Pad15)") (class "Default")
      (node (ref "U1") (pin "15") (pinfunction "P6.4_15") (pintype "bidirectional"))
    )
    (net (code "127") (name "unconnected-(U1-P6.5-Pad16)") (class "Default")
      (node (ref "U1") (pin "16") (pinfunction "P6.5_16") (pintype "bidirectional"))
    )
    (net (code "128") (name "unconnected-(U2-INT-Pad6)") (class "Default")
      (node (ref "U2") (pin "6") (pinfunction "INT_6") (pintype "output"))
    )
    (net (code "129") (name "unconnected-(U3-INT-Pad6)") (class "Default")
      (node (ref "U3") (pin "6") (pinfunction "INT_6") (pintype "output"))
    )
    (net (code "130") (name "unconnected-(U4-INT-Pad6)") (class "Default")
      (node (ref "U4") (pin "6") (pinfunction "INT_6") (pintype "output"))
    )
    (net (code "131") (name "unconnected-(U5-INT-Pad6)") (class "Default")
      (node (ref "U5") (pin "6") (pinfunction "INT_6") (pintype "output"))
    )
  )
)
